# Voltage_Divider_Brick.net
KiCad netlist of a schematic drawn in EAGLE
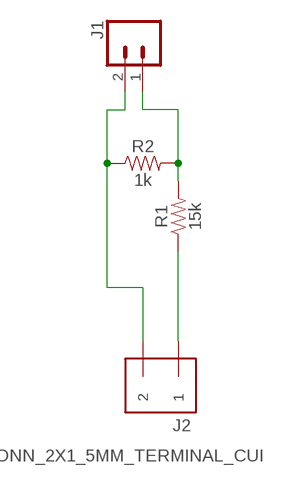
[diagram p0: schematic, sheet 1]

(export (version "E")
  (design (tool "Eeschema 10.0.6"))
  (components
    (comp (ref "J1")
      (value "CONN_02POLAR_LOCK")
      (footprint "eagle-import:MOLEX-1X2_LOCK")
      (libsource (lib "eagle-import") (part "CONN_02POLAR_LOCK"))
    )
    (comp (ref "J2")
      (value "CONN_2X1_5MM_TERMINAL_CUI")
      (footprint "eagle-import:CONN_2X1_5MM_TERMINAL_CUI_HOLE")
      (libsource (lib "eagle-import") (part "CONN_2X1_5MM_TERMINAL_CUI"))
    )
    (comp (ref "R1")
      (value "15k")
      (footprint "eagle-import:AXIAL-0.3")
      (libsource (lib "eagle-import") (part "15KOHM-HORIZ-1/4W-5%"))
    )
    (comp (ref "R2")
      (value "1k")
      (footprint "eagle-import:AXIAL-0.3")
      (libsource (lib "eagle-import") (part "1KOHM-HORIZ-1/4W-1%"))
    )
  )
  (nets
    (net (code "1") (name "Net-(J2-1)") (class "Default")
      (node (ref "J2") (pin "P$1") (pinfunction "1_P$1") (pintype "bidirectional"))
      (node (ref "R1") (pin "P$1") (pinfunction "1_P$1") (pintype "passive"))
    )
    (net (code "2") (name "Net-(J2-2)") (class "Default")
      (node (ref "J1") (pin "2") (pinfunction "2_2") (pintype "passive"))
      (node (ref "J2") (pin "P$2") (pinfunction "2_P$2") (pintype "bidirectional"))
      (node (ref "R2") (pin "P$1") (pinfunction "1_P$1") (pintype "passive"))
    )
    (net (code "3") (name "Net-(R1-2)") (class "Default")
      (node (ref "J1") (pin "1") (pinfunction "1_1") (pintype "passive"))
      (node (ref "R1") (pin "P$2") (pinfunction "2_P$2") (pintype "passive"))
      (node (ref "R2") (pin "P$2") (pinfunction "2_P$2") (pintype "passive"))
    )
  )
)
